# Driver2.net
KiCad netlist of a schematic drawn in Altium Designer
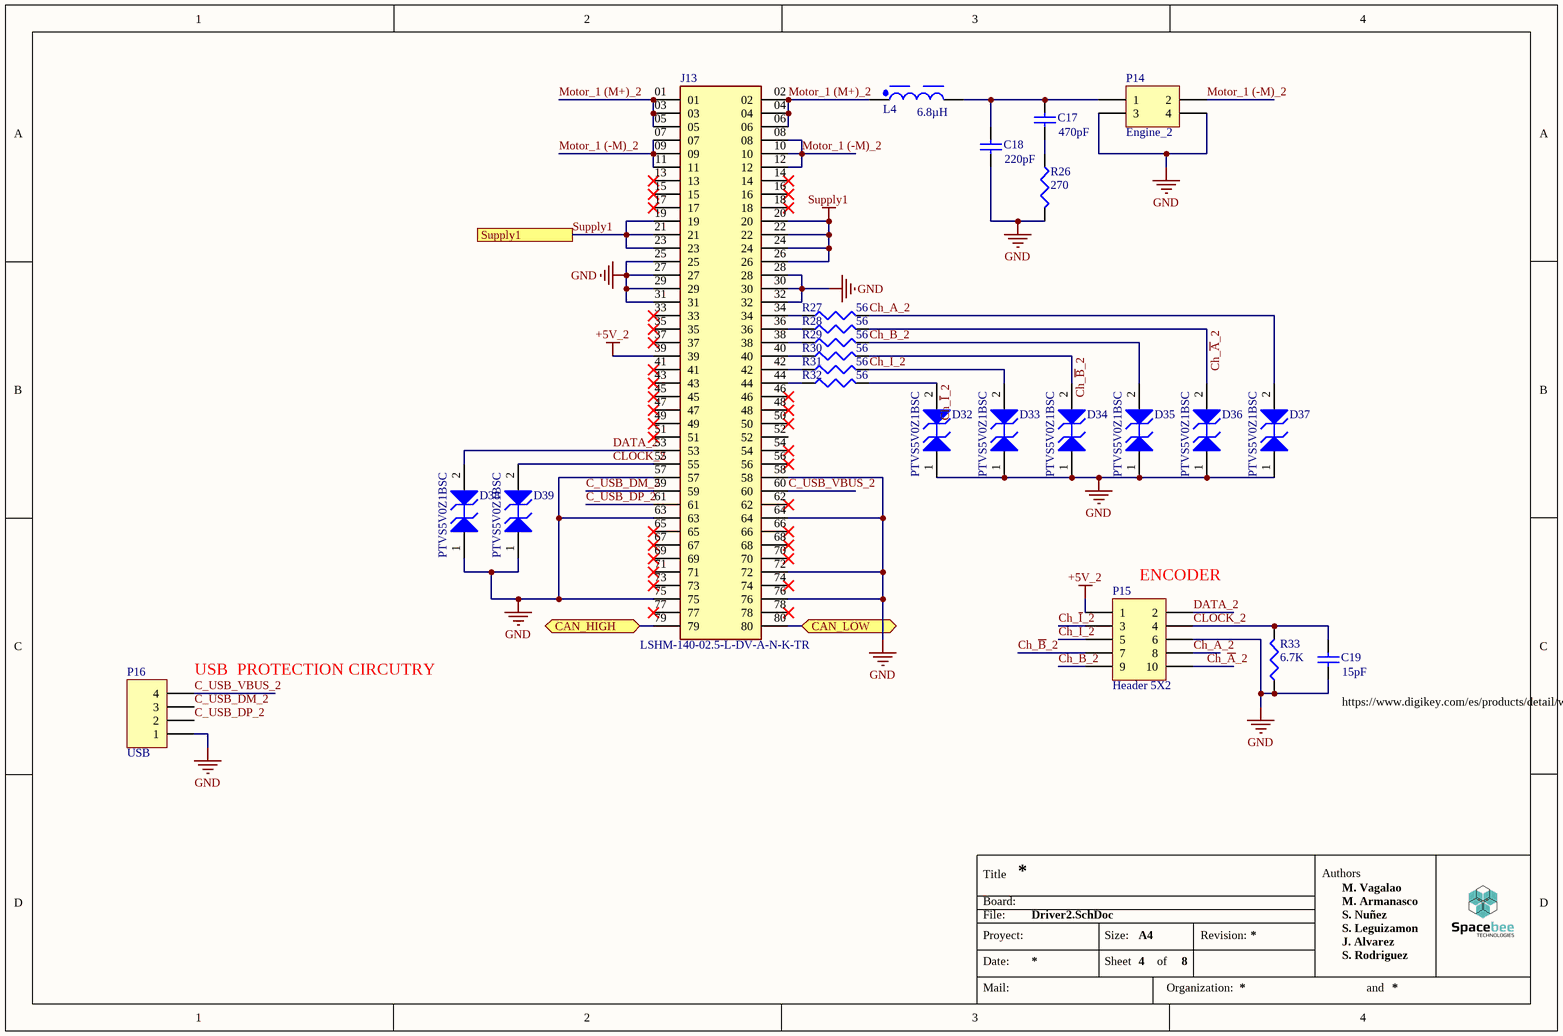
[diagram p0: Driver2.SchDoc]

(export (version "E")
  (design (tool "Eeschema 10.0.6"))
  (components
    (comp (ref "C17")
      (value "470pF")
      (footprint "1608[0603]")
      (description "Capacitor (Semiconductor SIM Model)")
      (fields (field (name "Comment") "Cap Semi") (field (name "PUBLISHER") "Altium Limited"))
      (libsource (lib "Miscellaneous Devices") (part "Cap Semi"))
    )
    (comp (ref "C18")
      (value "220pF")
      (footprint "1608[0603]")
      (description "Capacitor (Semiconductor SIM Model)")
      (fields (field (name "Comment") "Cap Semi") (field (name "PUBLISHER") "Altium Limited"))
      (libsource (lib "Miscellaneous Devices") (part "Cap Semi"))
    )
    (comp (ref "C19")
      (value "15pF")
      (footprint "1608[0603]")
      (description "Capacitor (Semiconductor SIM Model)")
      (fields (field (name "Comment") "Cap Semi") (field (name "PUBLISHER") "Altium Limited"))
      (libsource (lib "Miscellaneous Devices") (part "Cap Semi"))
    )
    (comp (ref "D32")
      (value "PTVS5V0Z1BSC")
      (footprint "SOD993B")
      (fields (field (name "MANUFACTURER") "On Semiconductor") (field (name "PARTNUMBER") "1SMB16CAT3"))
      (libsource (lib "DriverLib") (part "PTVS5V0Z1BSC"))
    )
    (comp (ref "D33")
      (value "PTVS5V0Z1BSC")
      (footprint "SOD993B")
      (fields (field (name "MANUFACTURER") "On Semiconductor") (field (name "PARTNUMBER") "1SMB16CAT3"))
      (libsource (lib "DriverLib") (part "PTVS5V0Z1BSC"))
    )
    (comp (ref "D34")
      (value "PTVS5V0Z1BSC")
      (footprint "SOD993B")
      (fields (field (name "MANUFACTURER") "On Semiconductor") (field (name "PARTNUMBER") "1SMB16CAT3"))
      (libsource (lib "DriverLib") (part "PTVS5V0Z1BSC"))
    )
    (comp (ref "D35")
      (value "PTVS5V0Z1BSC")
      (footprint "SOD993B")
      (fields (field (name "MANUFACTURER") "On Semiconductor") (field (name "PARTNUMBER") "1SMB16CAT3"))
      (libsource (lib "DriverLib") (part "PTVS5V0Z1BSC"))
    )
    (comp (ref "D36")
      (value "PTVS5V0Z1BSC")
      (footprint "SOD993B")
      (fields (field (name "MANUFACTURER") "On Semiconductor") (field (name "PARTNUMBER") "1SMB16CAT3"))
      (libsource (lib "DriverLib") (part "PTVS5V0Z1BSC"))
    )
    (comp (ref "D37")
      (value "PTVS5V0Z1BSC")
      (footprint "SOD993B")
      (fields (field (name "MANUFACTURER") "On Semiconductor") (field (name "PARTNUMBER") "1SMB16CAT3"))
      (libsource (lib "DriverLib") (part "PTVS5V0Z1BSC"))
    )
    (comp (ref "D38")
      (value "PTVS5V0Z1BSC")
      (footprint "SOD993B")
      (fields (field (name "MANUFACTURER") "On Semiconductor") (field (name "PARTNUMBER") "1SMB16CAT3"))
      (libsource (lib "DriverLib") (part "PTVS5V0Z1BSC"))
    )
    (comp (ref "D39")
      (value "PTVS5V0Z1BSC")
      (footprint "SOD993B")
      (fields (field (name "MANUFACTURER") "On Semiconductor") (field (name "PARTNUMBER") "1SMB16CAT3"))
      (libsource (lib "DriverLib") (part "PTVS5V0Z1BSC"))
    )
    (comp (ref "J13")
      (value "LSHM-140-02.5-L-DV-A-N-K-TR")
      (footprint "SAMTEC_LSHM-140-02.5-L-DV-A-N-K-TR")
      (description "LSHM - Samtec 0.50mm Razor Beam High-Speed Hermaphroditic Terminal / Socket Strip.")
      (libsource (lib "DriverLib") (part "LSHM-140-02.5-L-DV-A-N-K-TR"))
    )
    (comp (ref "L4")
      (value "6.8µH")
      (footprint "WE-XHMA_6060")
      (description "WE-XHMA SMD Power Inductor, size 1090, 6.8µH, 10.5A, 7.16mΩ")
      (fields
        (field (name "MANUFACTURER PART NUMBER") "78439369068")
        (field (name "MANUFACTURER") "Wurth Elektronik")
      )
      (libsource (lib "DriverLib") (part "78439369068"))
    )
    (comp (ref "P14")
      (value "Engine_2")
      (footprint "MOLEX_1724480004")
      (description "Header, 2-Pin, Dual row")
      (fields (field (name "PUBLISHER") "Altium Limited"))
      (libsource (lib "SpaceBee") (part "Header 2X2"))
    )
    (comp (ref "P15")
      (value "Header 5X2")
      (footprint "CONN_HIF3FC-14PA-2.54DS(71)_HIR")
      (description "Header, 5-Pin, Dual row")
      (fields (field (name "PUBLISHER") "Altium Limited"))
      (libsource (lib "DriverLib") (part "Header 5X2"))
    )
    (comp (ref "P16")
      (value "USB")
      (footprint "HDR1X4")
      (description "Header, 4-Pin")
      (fields (field (name "PUBLISHER") "Altium Limited"))
      (libsource (lib "Miscellaneous Connectors") (part "Header 4"))
    )
    (comp (ref "R26")
      (value "270")
      (footprint "J1-0603")
      (description "Resistor")
      (fields (field (name "Comment") "Res3") (field (name "PUBLISHER") "Altium Limited"))
      (libsource (lib "Miscellaneous Devices") (part "Res3"))
    )
    (comp (ref "R27")
      (value "56")
      (footprint "J1-0603")
      (description "Resistor")
      (fields (field (name "Comment") "Res3") (field (name "PUBLISHER") "Altium Limited"))
      (libsource (lib "Miscellaneous Devices") (part "Res3"))
    )
    (comp (ref "R28")
      (value "56")
      (footprint "J1-0603")
      (description "Resistor")
      (fields (field (name "Comment") "Res3") (field (name "PUBLISHER") "Altium Limited"))
      (libsource (lib "Miscellaneous Devices") (part "Res3"))
    )
    (comp (ref "R29")
      (value "56")
      (footprint "J1-0603")
      (description "Resistor")
      (fields (field (name "Comment") "Res3") (field (name "PUBLISHER") "Altium Limited"))
      (libsource (lib "Miscellaneous Devices") (part "Res3"))
    )
    (comp (ref "R30")
      (value "56")
      (footprint "J1-0603")
      (description "Resistor")
      (fields (field (name "Comment") "Res3") (field (name "PUBLISHER") "Altium Limited"))
      (libsource (lib "Miscellaneous Devices") (part "Res3"))
    )
    (comp (ref "R31")
      (value "56")
      (footprint "J1-0603")
      (description "Resistor")
      (fields (field (name "Comment") "Res3") (field (name "PUBLISHER") "Altium Limited"))
      (libsource (lib "Miscellaneous Devices") (part "Res3"))
    )
    (comp (ref "R32")
      (value "56")
      (footprint "J1-0603")
      (description "Resistor")
      (fields (field (name "Comment") "Res3") (field (name "PUBLISHER") "Altium Limited"))
      (libsource (lib "Miscellaneous Devices") (part "Res3"))
    )
    (comp (ref "R33")
      (value "6.7K")
      (footprint "J1-0603")
      (description "Resistor")
      (fields (field (name "Comment") "Res3") (field (name "PUBLISHER") "Altium Limited"))
      (libsource (lib "Miscellaneous Devices") (part "Res3"))
    )
  )
  (nets
    (net (code "1") (name "+5V_2") (class "Default")
      (node (ref "J13") (pin "39") (pinfunction "39_39") (pintype "passive"))
      (node (ref "P15") (pin "1") (pinfunction "1_1") (pintype "passive"))
    )
    (net (code "2") (name "/CAN_HIGH") (class "Default")
      (node (ref "J13") (pin "79") (pinfunction "79_79") (pintype "passive"))
    )
    (net (code "3") (name "/CAN_LOW") (class "Default")
      (node (ref "J13") (pin "80") (pinfunction "80_80") (pintype "passive"))
    )
    (net (code "4") (name "/CLOCK_2") (class "Default")
      (node (ref "C19") (pin "1") (pinfunction "1_1") (pintype "passive"))
      (node (ref "D39") (pin "2") (pinfunction "A2_2") (pintype "passive"))
      (node (ref "J13") (pin "55") (pinfunction "55_55") (pintype "passive"))
      (node (ref "P15") (pin "4") (pinfunction "4_4") (pintype "passive"))
      (node (ref "R33") (pin "2") (pinfunction "2_2") (pintype "passive"))
    )
    (net (code "5") (name "/C_USB_DM_2") (class "Default")
      (node (ref "J13") (pin "59") (pinfunction "59_59") (pintype "passive"))
      (node (ref "P16") (pin "3") (pinfunction "3_3") (pintype "passive"))
    )
    (net (code "6") (name "/C_USB_DP_2") (class "Default")
      (node (ref "J13") (pin "61") (pinfunction "61_61") (pintype "passive"))
      (node (ref "P16") (pin "2") (pinfunction "2_2") (pintype "passive"))
    )
    (net (code "7") (name "/C_USB_VBUS_2") (class "Default")
      (node (ref "J13") (pin "60") (pinfunction "60_60") (pintype "passive"))
      (node (ref "P16") (pin "4") (pinfunction "4_4") (pintype "passive"))
    )
    (net (code "8") (name "/Ch_A_2") (class "Default")
      (node (ref "D37") (pin "2") (pinfunction "A2_2") (pintype "passive"))
      (node (ref "P15") (pin "8") (pinfunction "8_8") (pintype "passive"))
      (node (ref "R27") (pin "2") (pinfunction "2_2") (pintype "passive"))
    )
    (net (code "9") (name "/Ch_B_2") (class "Default")
      (node (ref "D35") (pin "2") (pinfunction "A2_2") (pintype "passive"))
      (node (ref "P15") (pin "9") (pinfunction "9_9") (pintype "passive"))
      (node (ref "R29") (pin "2") (pinfunction "2_2") (pintype "passive"))
    )
    (net (code "10") (name "/Ch_I_2") (class "Default")
      (node (ref "D33") (pin "2") (pinfunction "A2_2") (pintype "passive"))
      (node (ref "P15") (pin "5") (pinfunction "5_5") (pintype "passive"))
      (node (ref "R31") (pin "2") (pinfunction "2_2") (pintype "passive"))
    )
    (net (code "11") (name "/Ch_~{A}_2") (class "Default")
      (node (ref "D36") (pin "2") (pinfunction "A2_2") (pintype "passive"))
      (node (ref "P15") (pin "10") (pinfunction "10_10") (pintype "passive"))
      (node (ref "R28") (pin "2") (pinfunction "2_2") (pintype "passive"))
    )
    (net (code "12") (name "/Ch_~{B}_2") (class "Default")
      (node (ref "D34") (pin "2") (pinfunction "A2_2") (pintype "passive"))
      (node (ref "P15") (pin "7") (pinfunction "7_7") (pintype "passive"))
      (node (ref "R30") (pin "2") (pinfunction "2_2") (pintype "passive"))
    )
    (net (code "13") (name "/Ch_~{I}_2") (class "Default")
      (node (ref "D32") (pin "2") (pinfunction "A2_2") (pintype "passive"))
      (node (ref "P15") (pin "3") (pinfunction "3_3") (pintype "passive"))
      (node (ref "R32") (pin "2") (pinfunction "2_2") (pintype "passive"))
    )
    (net (code "14") (name "/DATA_2") (class "Default")
      (node (ref "D38") (pin "2") (pinfunction "A2_2") (pintype "passive"))
      (node (ref "J13") (pin "53") (pinfunction "53_53") (pintype "passive"))
      (node (ref "P15") (pin "2") (pinfunction "2_2") (pintype "passive"))
    )
    (net (code "15") (name "/Motor_1 (-M)_2") (class "Default")
      (node (ref "J13") (pin "07") (pinfunction "07_07") (pintype "passive"))
      (node (ref "J13") (pin "08") (pinfunction "08_08") (pintype "passive"))
      (node (ref "J13") (pin "09") (pinfunction "09_09") (pintype "passive"))
      (node (ref "J13") (pin "10") (pinfunction "10_10") (pintype "passive"))
      (node (ref "J13") (pin "11") (pinfunction "11_11") (pintype "passive"))
      (node (ref "J13") (pin "12") (pinfunction "12_12") (pintype "passive"))
      (node (ref "P14") (pin "2") (pinfunction "2_2") (pintype "passive"))
    )
    (net (code "16") (name "/Motor_1 (M+)_2") (class "Default")
      (node (ref "J13") (pin "01") (pinfunction "01_01") (pintype "passive"))
      (node (ref "J13") (pin "02") (pinfunction "02_02") (pintype "passive"))
      (node (ref "J13") (pin "03") (pinfunction "03_03") (pintype "passive"))
      (node (ref "J13") (pin "04") (pinfunction "04_04") (pintype "passive"))
      (node (ref "J13") (pin "05") (pinfunction "05_05") (pintype "passive"))
      (node (ref "J13") (pin "06") (pinfunction "06_06") (pintype "passive"))
      (node (ref "L4") (pin "1") (pinfunction "1_1") (pintype "passive"))
    )
    (net (code "17") (name "GND") (class "Default")
      (node (ref "C18") (pin "2") (pinfunction "2_2") (pintype "passive"))
      (node (ref "C19") (pin "2") (pinfunction "2_2") (pintype "passive"))
      (node (ref "D32") (pin "1") (pinfunction "A1_1") (pintype "passive"))
      (node (ref "D33") (pin "1") (pinfunction "A1_1") (pintype "passive"))
      (node (ref "D34") (pin "1") (pinfunction "A1_1") (pintype "passive"))
      (node (ref "D35") (pin "1") (pinfunction "A1_1") (pintype "passive"))
      (node (ref "D36") (pin "1") (pinfunction "A1_1") (pintype "passive"))
      (node (ref "D37") (pin "1") (pinfunction "A1_1") (pintype "passive"))
      (node (ref "D38") (pin "1") (pinfunction "A1_1") (pintype "passive"))
      (node (ref "D39") (pin "1") (pinfunction "A1_1") (pintype "passive"))
      (node (ref "J13") (pin "25") (pinfunction "25_25") (pintype "passive"))
      (node (ref "J13") (pin "27") (pinfunction "27_27") (pintype "passive"))
      (node (ref "J13") (pin "28") (pinfunction "28_28") (pintype "passive"))
      (node (ref "J13") (pin "29") (pinfunction "29_29") (pintype "passive"))
      (node (ref "J13") (pin "30") (pinfunction "30_30") (pintype "passive"))
      (node (ref "J13") (pin "31") (pinfunction "31_31") (pintype "passive"))
      (node (ref "J13") (pin "32") (pinfunction "32_32") (pintype "passive"))
      (node (ref "J13") (pin "57") (pinfunction "57_57") (pintype "passive"))
      (node (ref "J13") (pin "58") (pinfunction "58_58") (pintype "passive"))
      (node (ref "J13") (pin "63") (pinfunction "63_63") (pintype "passive"))
      (node (ref "J13") (pin "64") (pinfunction "64_64") (pintype "passive"))
      (node (ref "J13") (pin "72") (pinfunction "72_72") (pintype "passive"))
      (node (ref "J13") (pin "75") (pinfunction "75_75") (pintype "passive"))
      (node (ref "J13") (pin "76") (pinfunction "76_76") (pintype "passive"))
      (node (ref "P14") (pin "3") (pinfunction "3_3") (pintype "passive"))
      (node (ref "P14") (pin "4") (pinfunction "4_4") (pintype "passive"))
      (node (ref "P15") (pin "6") (pinfunction "6_6") (pintype "passive"))
      (node (ref "P16") (pin "1") (pinfunction "1_1") (pintype "passive"))
      (node (ref "R26") (pin "2") (pinfunction "2_2") (pintype "passive"))
      (node (ref "R33") (pin "1") (pinfunction "1_1") (pintype "passive"))
    )
    (net (code "18") (name "Net-(C17-Pad1)") (class "Default")
      (node (ref "C17") (pin "1") (pinfunction "1_1") (pintype "passive"))
      (node (ref "C18") (pin "1") (pinfunction "1_1") (pintype "passive"))
      (node (ref "L4") (pin "2") (pinfunction "2_2") (pintype "passive"))
      (node (ref "P14") (pin "1") (pinfunction "1_1") (pintype "passive"))
    )
    (net (code "19") (name "Net-(C17-Pad2)") (class "Default")
      (node (ref "C17") (pin "2") (pinfunction "2_2") (pintype "passive"))
      (node (ref "R26") (pin "1") (pinfunction "1_1") (pintype "passive"))
    )
    (net (code "20") (name "Net-(J13-Pad34)") (class "Default")
      (node (ref "J13") (pin "34") (pinfunction "34_34") (pintype "passive"))
      (node (ref "R27") (pin "1") (pinfunction "1_1") (pintype "passive"))
    )
    (net (code "21") (name "Net-(J13-Pad36)") (class "Default")
      (node (ref "J13") (pin "36") (pinfunction "36_36") (pintype "passive"))
      (node (ref "R28") (pin "1") (pinfunction "1_1") (pintype "passive"))
    )
    (net (code "22") (name "Net-(J13-Pad38)") (class "Default")
      (node (ref "J13") (pin "38") (pinfunction "38_38") (pintype "passive"))
      (node (ref "R29") (pin "1") (pinfunction "1_1") (pintype "passive"))
    )
    (net (code "23") (name "Net-(J13-Pad40)") (class "Default")
      (node (ref "J13") (pin "40") (pinfunction "40_40") (pintype "passive"))
      (node (ref "R30") (pin "1") (pinfunction "1_1") (pintype "passive"))
    )
    (net (code "24") (name "Net-(J13-Pad42)") (class "Default")
      (node (ref "J13") (pin "42") (pinfunction "42_42") (pintype "passive"))
      (node (ref "R31") (pin "1") (pinfunction "1_1") (pintype "passive"))
    )
    (net (code "25") (name "Net-(J13-Pad44)") (class "Default")
      (node (ref "J13") (pin "44") (pinfunction "44_44") (pintype "passive"))
      (node (ref "R32") (pin "1") (pinfunction "1_1") (pintype "passive"))
    )
    (net (code "26") (name "Supply1") (class "Default")
      (node (ref "J13") (pin "19") (pinfunction "19_19") (pintype "passive"))
      (node (ref "J13") (pin "20") (pinfunction "20_20") (pintype "passive"))
      (node (ref "J13") (pin "21") (pinfunction "21_21") (pintype "passive"))
      (node (ref "J13") (pin "22") (pinfunction "22_22") (pintype "passive"))
      (node (ref "J13") (pin "23") (pinfunction "23_23") (pintype "passive"))
      (node (ref "J13") (pin "24") (pinfunction "24_24") (pintype "passive"))
      (node (ref "J13") (pin "26") (pinfunction "26_26") (pintype "passive"))
    )
    (net (code "27") (name "unconnected-(J13-Pad13)") (class "Default")
      (node (ref "J13") (pin "13") (pinfunction "13_13") (pintype "passive+no_connect"))
    )
    (net (code "28") (name "unconnected-(J13-Pad14)") (class "Default")
      (node (ref "J13") (pin "14") (pinfunction "14_14") (pintype "passive+no_connect"))
    )
    (net (code "29") (name "unconnected-(J13-Pad15)") (class "Default")
      (node (ref "J13") (pin "15") (pinfunction "15_15") (pintype "passive+no_connect"))
    )
    (net (code "30") (name "unconnected-(J13-Pad16)") (class "Default")
      (node (ref "J13") (pin "16") (pinfunction "16_16") (pintype "passive+no_connect"))
    )
    (net (code "31") (name "unconnected-(J13-Pad17)") (class "Default")
      (node (ref "J13") (pin "17") (pinfunction "17_17") (pintype "passive+no_connect"))
    )
    (net (code "32") (name "unconnected-(J13-Pad18)") (class "Default")
      (node (ref "J13") (pin "18") (pinfunction "18_18") (pintype "passive+no_connect"))
    )
    (net (code "33") (name "unconnected-(J13-Pad33)") (class "Default")
      (node (ref "J13") (pin "33") (pinfunction "33_33") (pintype "passive+no_connect"))
    )
    (net (code "34") (name "unconnected-(J13-Pad35)") (class "Default")
      (node (ref "J13") (pin "35") (pinfunction "35_35") (pintype "passive+no_connect"))
    )
    (net (code "35") (name "unconnected-(J13-Pad37)") (class "Default")
      (node (ref "J13") (pin "37") (pinfunction "37_37") (pintype "passive+no_connect"))
    )
    (net (code "36") (name "unconnected-(J13-Pad41)") (class "Default")
      (node (ref "J13") (pin "41") (pinfunction "41_41") (pintype "passive+no_connect"))
    )
    (net (code "37") (name "unconnected-(J13-Pad43)") (class "Default")
      (node (ref "J13") (pin "43") (pinfunction "43_43") (pintype "passive+no_connect"))
    )
    (net (code "38") (name "unconnected-(J13-Pad45)") (class "Default")
      (node (ref "J13") (pin "45") (pinfunction "45_45") (pintype "passive+no_connect"))
    )
    (net (code "39") (name "unconnected-(J13-Pad46)") (class "Default")
      (node (ref "J13") (pin "46") (pinfunction "46_46") (pintype "passive+no_connect"))
    )
    (net (code "40") (name "unconnected-(J13-Pad47)") (class "Default")
      (node (ref "J13") (pin "47") (pinfunction "47_47") (pintype "passive+no_connect"))
    )
    (net (code "41") (name "unconnected-(J13-Pad48)") (class "Default")
      (node (ref "J13") (pin "48") (pinfunction "48_48") (pintype "passive+no_connect"))
    )
    (net (code "42") (name "unconnected-(J13-Pad49)") (class "Default")
      (node (ref "J13") (pin "49") (pinfunction "49_49") (pintype "passive+no_connect"))
    )
    (net (code "43") (name "unconnected-(J13-Pad50)") (class "Default")
      (node (ref "J13") (pin "50") (pinfunction "50_50") (pintype "passive+no_connect"))
    )
    (net (code "44") (name "unconnected-(J13-Pad51)") (class "Default")
      (node (ref "J13") (pin "51") (pinfunction "51_51") (pintype "passive+no_connect"))
    )
    (net (code "45") (name "unconnected-(J13-Pad52)") (class "Default")
      (node (ref "J13") (pin "52") (pinfunction "52_52") (pintype "passive"))
    )
    (net (code "46") (name "unconnected-(J13-Pad54)") (class "Default")
      (node (ref "J13") (pin "54") (pinfunction "54_54") (pintype "passive+no_connect"))
    )
    (net (code "47") (name "unconnected-(J13-Pad56)") (class "Default")
      (node (ref "J13") (pin "56") (pinfunction "56_56") (pintype "passive+no_connect"))
    )
    (net (code "48") (name "unconnected-(J13-Pad62)") (class "Default")
      (node (ref "J13") (pin "62") (pinfunction "62_62") (pintype "passive+no_connect"))
    )
    (net (code "49") (name "unconnected-(J13-Pad65)") (class "Default")
      (node (ref "J13") (pin "65") (pinfunction "65_65") (pintype "passive+no_connect"))
    )
    (net (code "50") (name "unconnected-(J13-Pad66)") (class "Default")
      (node (ref "J13") (pin "66") (pinfunction "66_66") (pintype "passive+no_connect"))
    )
    (net (code "51") (name "unconnected-(J13-Pad67)") (class "Default")
      (node (ref "J13") (pin "67") (pinfunction "67_67") (pintype "passive+no_connect"))
    )
    (net (code "52") (name "unconnected-(J13-Pad68)") (class "Default")
      (node (ref "J13") (pin "68") (pinfunction "68_68") (pintype "passive+no_connect"))
    )
    (net (code "53") (name "unconnected-(J13-Pad69)") (class "Default")
      (node (ref "J13") (pin "69") (pinfunction "69_69") (pintype "passive+no_connect"))
    )
    (net (code "54") (name "unconnected-(J13-Pad70)") (class "Default")
      (node (ref "J13") (pin "70") (pinfunction "70_70") (pintype "passive+no_connect"))
    )
    (net (code "55") (name "unconnected-(J13-Pad71)") (class "Default")
      (node (ref "J13") (pin "71") (pinfunction "71_71") (pintype "passive+no_connect"))
    )
    (net (code "56") (name "unconnected-(J13-Pad73)") (class "Default")
      (node (ref "J13") (pin "73") (pinfunction "73_73") (pintype "passive+no_connect"))
    )
    (net (code "57") (name "unconnected-(J13-Pad74)") (class "Default")
      (node (ref "J13") (pin "74") (pinfunction "74_74") (pintype "passive+no_connect"))
    )
    (net (code "58") (name "unconnected-(J13-Pad77)") (class "Default")
      (node (ref "J13") (pin "77") (pinfunction "77_77") (pintype "passive+no_connect"))
    )
    (net (code "59") (name "unconnected-(J13-Pad78)") (class "Default")
      (node (ref "J13") (pin "78") (pinfunction "78_78") (pintype "passive+no_connect"))
    )
  )
)
